# main.net
KiCad netlist of a schematic drawn in Altium Designer
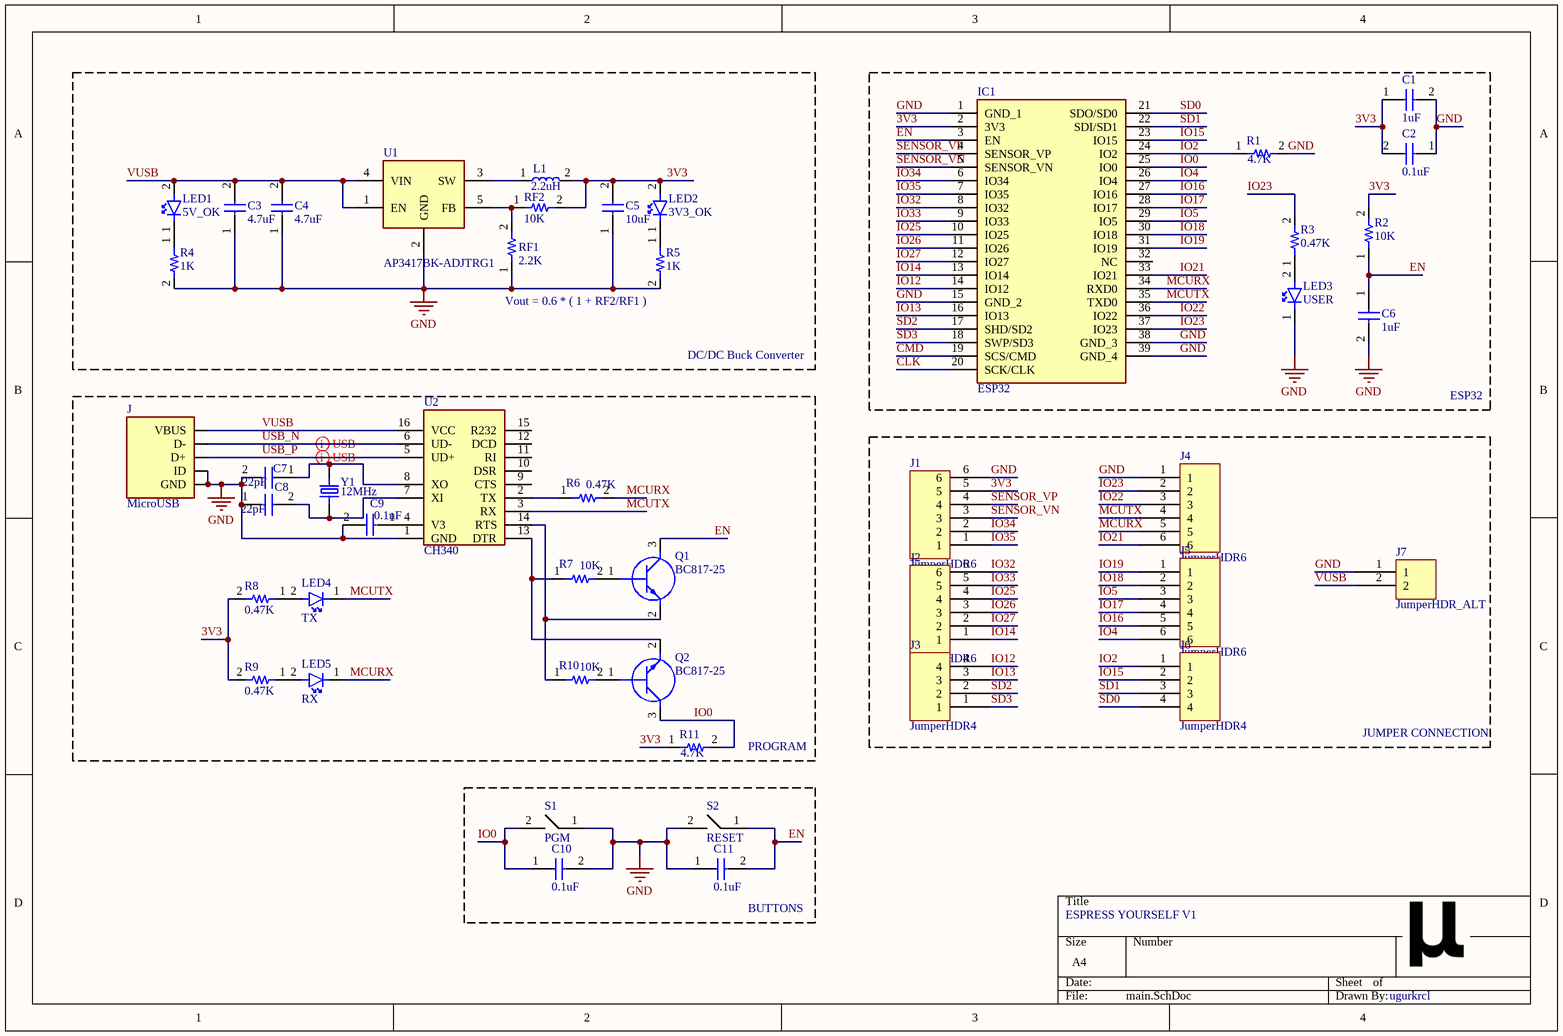
[diagram p0: main.SchDoc]

(export (version "E")
  (design (tool "Eeschema 10.0.6"))
  (components
    (comp (ref "C1")
      (value "1uF")
      (footprint "0805 Capacitor")
      (description "Capacitor")
      (fields
        (field (name "MANUFACTURER_PART_NUMBER") "C3216C0G1H682J060AA")
        (field (name "MOUSER PART NUMBER") "810-C3216C0G1H682J-1")
      )
      (libsource (lib "uAltiumLib") (part "0805 Capacitor"))
    )
    (comp (ref "C2")
      (value "0.1uF")
      (footprint "0603 Capacitor")
      (description "Capacitor")
      (fields
        (field (name "MANUFACTURER_PART_NUMBER") "06031A120JAT2A")
        (field (name "MOUSER PART NUMBER") "581-06031A120J")
      )
      (libsource (lib "uAltiumLib") (part "0603 Capacitor"))
    )
    (comp (ref "C3")
      (value "4.7uF")
      (footprint "0805 Capacitor")
      (description "Capacitor")
      (fields
        (field (name "MANUFACTURER_PART_NUMBER") "C3216C0G1H682J060AA")
        (field (name "MOUSER PART NUMBER") "810-C3216C0G1H682J-1")
      )
      (libsource (lib "uAltiumLib") (part "0805 Capacitor"))
    )
    (comp (ref "C4")
      (value "4.7uF")
      (footprint "0805 Capacitor")
      (description "Capacitor")
      (fields
        (field (name "MANUFACTURER_PART_NUMBER") "C3216C0G1H682J060AA")
        (field (name "MOUSER PART NUMBER") "810-C3216C0G1H682J-1")
      )
      (libsource (lib "uAltiumLib") (part "0805 Capacitor"))
    )
    (comp (ref "C5")
      (value "10uF")
      (footprint "0805 Capacitor")
      (description "Capacitor")
      (fields
        (field (name "MANUFACTURER_PART_NUMBER") "C3216C0G1H682J060AA")
        (field (name "MOUSER PART NUMBER") "810-C3216C0G1H682J-1")
      )
      (libsource (lib "uAltiumLib") (part "0805 Capacitor"))
    )
    (comp (ref "C6")
      (value "1uF")
      (footprint "0603 Capacitor")
      (description "Capacitor")
      (fields
        (field (name "MANUFACTURER_PART_NUMBER") "06031A120JAT2A")
        (field (name "MOUSER PART NUMBER") "581-06031A120J")
      )
      (libsource (lib "uAltiumLib") (part "0603 Capacitor"))
    )
    (comp (ref "C7")
      (value "22pF")
      (footprint "0603 Capacitor")
      (description "Capacitor")
      (fields
        (field (name "MANUFACTURER_PART_NUMBER") "06031A120JAT2A")
        (field (name "MOUSER PART NUMBER") "581-06031A120J")
      )
      (libsource (lib "uAltiumLib") (part "0603 Capacitor"))
    )
    (comp (ref "C8")
      (value "22pF")
      (footprint "0603 Capacitor")
      (description "Capacitor")
      (fields
        (field (name "MANUFACTURER_PART_NUMBER") "06031A120JAT2A")
        (field (name "MOUSER PART NUMBER") "581-06031A120J")
      )
      (libsource (lib "uAltiumLib") (part "0603 Capacitor"))
    )
    (comp (ref "C9")
      (value "0.1uF")
      (footprint "0603 Capacitor")
      (description "Capacitor")
      (fields
        (field (name "MANUFACTURER_PART_NUMBER") "06031A120JAT2A")
        (field (name "MOUSER PART NUMBER") "581-06031A120J")
      )
      (libsource (lib "uAltiumLib") (part "0603 Capacitor"))
    )
    (comp (ref "C10")
      (value "0.1uF")
      (footprint "0603 Capacitor")
      (description "Capacitor")
      (fields
        (field (name "MANUFACTURER_PART_NUMBER") "06031A120JAT2A")
        (field (name "MOUSER PART NUMBER") "581-06031A120J")
      )
      (libsource (lib "uAltiumLib") (part "0603 Capacitor"))
    )
    (comp (ref "C11")
      (value "0.1uF")
      (footprint "0603 Capacitor")
      (description "Capacitor")
      (fields
        (field (name "MANUFACTURER_PART_NUMBER") "06031A120JAT2A")
        (field (name "MOUSER PART NUMBER") "581-06031A120J")
      )
      (libsource (lib "uAltiumLib") (part "0603 Capacitor"))
    )
    (comp (ref "IC1")
      (value "ESP32")
      (footprint "ESP32")
      (description "Integrated Circuit")
      (fields
        (field (name "MANUFACTURER_PART_NUMBER") "ESP-WROOM-32D")
        (field (name "MOUSER PART NUMBER") "356-ESP-WROOM-32D")
      )
      (libsource (lib "uAltiumLib") (part "ESP32"))
    )
    (comp (ref "J")
      (value "MicroUSB")
      (footprint "MicroUSB")
      (fields (field (name "MP") "ZX62-B-5PA") (field (name "MF") "Hirose"))
      (libsource (lib "uAltiumLib") (part "MicroUSB"))
    )
    (comp (ref "J1")
      (value "JumperHDR6")
      (footprint "JumperHDR6")
      (libsource (lib "uAltiumLib") (part "JumperHDR6"))
    )
    (comp (ref "J2")
      (value "JumperHDR6")
      (footprint "JumperHDR6")
      (libsource (lib "uAltiumLib") (part "JumperHDR6"))
    )
    (comp (ref "J3")
      (value "JumperHDR4")
      (footprint "JumperHDR4")
      (libsource (lib "uAltiumLib") (part "JumperHDR4"))
    )
    (comp (ref "J4") (value "JumperHDR6") (footprint "JumperHDR6") (libsource (lib "") (part "JumperHDR6_1")))
    (comp (ref "J5") (value "JumperHDR6") (footprint "JumperHDR6") (libsource (lib "") (part "JumperHDR6_1")))
    (comp (ref "J6") (value "JumperHDR4") (footprint "JumperHDR4") (libsource (lib "") (part "JumperHDR4_1")))
    (comp (ref "J7")
      (value "JumperHDR_ALT")
      (footprint "JumperHDR")
      (libsource (lib "Schlib1") (part "JumperHDR_ALT"))
    )
    (comp (ref "L1")
      (value "2.2uH")
      (footprint "PcbLib1:INDUCTOR_3x3.5")
      (description "Inductor")
      (fields (field (name "MANUFACTURER_PART_NUMBER") "CD32-4R7M"))
      (libsource (lib "Schlib1") (part "INDUCTOR_3x3.5"))
    )
    (comp (ref "LED1")
      (value "5V_OK")
      (footprint "0603 LED")
      (description "LED")
      (fields
        (field (name "MANUFACTURER_PART_NUMBER") "150060GS55040")
        (field (name "MOUSER PART NUMBER") "710-150060GS55040")
      )
      (libsource (lib "Schlib1") (part "0603 LED"))
    )
    (comp (ref "LED2")
      (value "3V3_OK")
      (footprint "0603 LED")
      (description "LED")
      (fields
        (field (name "MANUFACTURER_PART_NUMBER") "150060GS55040")
        (field (name "MOUSER PART NUMBER") "710-150060GS55040")
      )
      (libsource (lib "Schlib1") (part "0603 LED"))
    )
    (comp (ref "LED3")
      (value "USER")
      (footprint "0603 LED")
      (description "LED")
      (fields
        (field (name "MANUFACTURER_PART_NUMBER") "150060GS55040")
        (field (name "MOUSER PART NUMBER") "710-150060GS55040")
      )
      (libsource (lib "Schlib1") (part "0603 LED"))
    )
    (comp (ref "LED4")
      (value "TX")
      (footprint "0603 LED")
      (description "LED")
      (fields
        (field (name "MANUFACTURER_PART_NUMBER") "150060GS55040")
        (field (name "MOUSER PART NUMBER") "710-150060GS55040")
      )
      (libsource (lib "Schlib1") (part "0603 LED"))
    )
    (comp (ref "LED5")
      (value "RX")
      (footprint "0603 LED")
      (description "LED")
      (fields
        (field (name "MANUFACTURER_PART_NUMBER") "150060GS55040")
        (field (name "MOUSER PART NUMBER") "710-150060GS55040")
      )
      (libsource (lib "Schlib1") (part "0603 LED"))
    )
    (comp (ref "Q1")
      (value "BC817-25")
      (footprint "BC817")
      (description "Transistor BJT NPN")
      (libsource (lib "uAltiumLib") (part "BC817-25"))
    )
    (comp (ref "Q2")
      (value "BC817-25")
      (footprint "BC817")
      (description "Transistor BJT NPN")
      (libsource (lib "uAltiumLib") (part "BC817-25"))
    )
    (comp (ref "R1")
      (value "4.7K")
      (footprint "0603 Resistor")
      (description "Resistor")
      (fields
        (field (name "MANUFACTURER_PART_NUMBER") "CPF0603B100RE1")
        (field (name "MOUSER PART NUMBER") "279-CPF0603B100RE1")
      )
      (libsource (lib "uAltiumLib") (part "0603 Resistor"))
    )
    (comp (ref "R2")
      (value "10K")
      (footprint "0603 Resistor")
      (description "Resistor")
      (fields
        (field (name "MANUFACTURER_PART_NUMBER") "CPF0603B100RE1")
        (field (name "MOUSER PART NUMBER") "279-CPF0603B100RE1")
      )
      (libsource (lib "uAltiumLib") (part "0603 Resistor"))
    )
    (comp (ref "R3")
      (value "0.47K")
      (footprint "0603 Resistor")
      (description "Resistor")
      (fields
        (field (name "MANUFACTURER_PART_NUMBER") "CPF0603B100RE1")
        (field (name "MOUSER PART NUMBER") "279-CPF0603B100RE1")
      )
      (libsource (lib "uAltiumLib") (part "0603 Resistor"))
    )
    (comp (ref "R4")
      (value "1K")
      (footprint "0603 Resistor")
      (description "Resistor")
      (fields
        (field (name "MANUFACTURER_PART_NUMBER") "CPF0603B100RE1")
        (field (name "MOUSER PART NUMBER") "279-CPF0603B100RE1")
      )
      (libsource (lib "uAltiumLib") (part "0603 Resistor"))
    )
    (comp (ref "R5")
      (value "1K")
      (footprint "0603 Resistor")
      (description "Resistor")
      (fields
        (field (name "MANUFACTURER_PART_NUMBER") "CPF0603B100RE1")
        (field (name "MOUSER PART NUMBER") "279-CPF0603B100RE1")
      )
      (libsource (lib "uAltiumLib") (part "0603 Resistor"))
    )
    (comp (ref "R6")
      (value "0.47K")
      (footprint "0603 Resistor")
      (description "Resistor")
      (fields
        (field (name "MANUFACTURER_PART_NUMBER") "CPF0603B100RE1")
        (field (name "MOUSER PART NUMBER") "279-CPF0603B100RE1")
      )
      (libsource (lib "uAltiumLib") (part "0603 Resistor"))
    )
    (comp (ref "R7")
      (value "10K")
      (footprint "0603 Resistor")
      (description "Resistor")
      (fields
        (field (name "MANUFACTURER_PART_NUMBER") "CPF0603B100RE1")
        (field (name "MOUSER PART NUMBER") "279-CPF0603B100RE1")
      )
      (libsource (lib "uAltiumLib") (part "0603 Resistor"))
    )
    (comp (ref "R8")
      (value "0.47K")
      (footprint "0603 Resistor")
      (description "Resistor")
      (fields
        (field (name "MANUFACTURER_PART_NUMBER") "CPF0603B100RE1")
        (field (name "MOUSER PART NUMBER") "279-CPF0603B100RE1")
      )
      (libsource (lib "uAltiumLib") (part "0603 Resistor"))
    )
    (comp (ref "R9")
      (value "0.47K")
      (footprint "0603 Resistor")
      (description "Resistor")
      (fields
        (field (name "MANUFACTURER_PART_NUMBER") "CPF0603B100RE1")
        (field (name "MOUSER PART NUMBER") "279-CPF0603B100RE1")
      )
      (libsource (lib "uAltiumLib") (part "0603 Resistor"))
    )
    (comp (ref "R10")
      (value "10K")
      (footprint "0603 Resistor")
      (description "Resistor")
      (fields
        (field (name "MANUFACTURER_PART_NUMBER") "CPF0603B100RE1")
        (field (name "MOUSER PART NUMBER") "279-CPF0603B100RE1")
      )
      (libsource (lib "uAltiumLib") (part "0603 Resistor"))
    )
    (comp (ref "R11")
      (value "4.7K")
      (footprint "0603 Resistor")
      (description "Resistor")
      (fields
        (field (name "MANUFACTURER_PART_NUMBER") "CPF0603B100RE1")
        (field (name "MOUSER PART NUMBER") "279-CPF0603B100RE1")
      )
      (libsource (lib "uAltiumLib") (part "0603 Resistor"))
    )
    (comp (ref "RF1")
      (value "2.2K")
      (footprint "0603 Resistor")
      (description "Resistor")
      (fields
        (field (name "MANUFACTURER_PART_NUMBER") "CPF0603B100RE1")
        (field (name "MOUSER PART NUMBER") "279-CPF0603B100RE1")
      )
      (libsource (lib "uAltiumLib") (part "0603 Resistor"))
    )
    (comp (ref "RF2")
      (value "10K")
      (footprint "0603 Resistor")
      (description "Resistor")
      (fields
        (field (name "MANUFACTURER_PART_NUMBER") "CPF0603B100RE1")
        (field (name "MOUSER PART NUMBER") "279-CPF0603B100RE1")
      )
      (libsource (lib "uAltiumLib") (part "0603 Resistor"))
    )
    (comp (ref "S1")
      (value "PGM")
      (footprint "TACT SWITCH SMD")
      (fields (field (name "MP") "B3F-1000") (field (name "MF") "Omron"))
      (libsource (lib "uAltiumLib") (part "TACT SWITCH SMD"))
    )
    (comp (ref "S2")
      (value "RESET")
      (footprint "TACT SWITCH SMD")
      (fields (field (name "MP") "B3F-1000") (field (name "MF") "Omron"))
      (libsource (lib "uAltiumLib") (part "TACT SWITCH SMD"))
    )
    (comp (ref "U1")
      (value "AP3417BK-ADJTRG1")
      (footprint "SOT BUCK")
      (description "Power Supply")
      (fields (field (name "MOUSER PART NUMBER") "621-AP3417BK-ADJTRG1"))
      (libsource (lib "Schlib1") (part "AP3417BK-ADJTRG1"))
    )
    (comp (ref "U2")
      (value "CH340")
      (footprint "ch340g-SOIC16")
      (fields (field (name "MF") "Eaton"))
      (libsource (lib "Schlib1") (part "CH340"))
    )
    (comp (ref "Y1")
      (value "12MHz")
      (footprint "Crystal-HC49")
      (fields
        (field (name "DIGI-KEY_PART_NUMBER") "X1115-ND")
        (field (name "MF") "ECS Inc.")
        (field (name "MP") "ECS-80-18-4XDN")
      )
      (libsource (lib "uAltiumLib") (part "HC49 Crystal"))
    )
  )
  (nets
    (net (code "1") (name "/3V3") (class "Default")
      (node (ref "C1") (pin "1") (pinfunction "1_1") (pintype "passive"))
      (node (ref "C2") (pin "2") (pinfunction "2_2") (pintype "passive"))
      (node (ref "C5") (pin "2") (pinfunction "2_2") (pintype "passive"))
      (node (ref "IC1") (pin "2") (pinfunction "3V3_2") (pintype "passive"))
      (node (ref "J1") (pin "5") (pinfunction "5_5") (pintype "passive"))
      (node (ref "L1") (pin "2") (pinfunction "2_2") (pintype "passive"))
      (node (ref "LED2") (pin "2") (pinfunction "A_2") (pintype "passive"))
      (node (ref "R11") (pin "1") (pinfunction "1_1") (pintype "passive"))
      (node (ref "R2") (pin "2") (pinfunction "2_2") (pintype "passive"))
      (node (ref "R8") (pin "2") (pinfunction "2_2") (pintype "passive"))
      (node (ref "R9") (pin "2") (pinfunction "2_2") (pintype "passive"))
      (node (ref "RF2") (pin "2") (pinfunction "2_2") (pintype "passive"))
    )
    (net (code "2") (name "/CLK") (class "Default")
      (node (ref "IC1") (pin "20") (pinfunction "SCK/CLK_20") (pintype "passive"))
    )
    (net (code "3") (name "/CMD") (class "Default")
      (node (ref "IC1") (pin "19") (pinfunction "SCS/CMD_19") (pintype "passive"))
    )
    (net (code "4") (name "/EN") (class "Default")
      (node (ref "C11") (pin "2") (pinfunction "2_2") (pintype "passive"))
      (node (ref "C6") (pin "1") (pinfunction "1_1") (pintype "passive"))
      (node (ref "IC1") (pin "3") (pinfunction "EN_3") (pintype "passive"))
      (node (ref "Q1") (pin "3") (pinfunction "C_3") (pintype "passive"))
      (node (ref "R2") (pin "1") (pinfunction "1_1") (pintype "passive"))
      (node (ref "S2") (pin "1") (pintype "passive"))
    )
    (net (code "5") (name "/IO0") (class "Default")
      (node (ref "C10") (pin "1") (pinfunction "1_1") (pintype "passive"))
      (node (ref "IC1") (pin "25") (pinfunction "IO0_25") (pintype "passive"))
      (node (ref "Q2") (pin "3") (pinfunction "C_3") (pintype "passive"))
      (node (ref "R11") (pin "2") (pinfunction "2_2") (pintype "passive"))
      (node (ref "S1") (pin "2") (pintype "passive"))
    )
    (net (code "6") (name "/IO2") (class "Default")
      (node (ref "IC1") (pin "24") (pinfunction "IO2_24") (pintype "passive"))
      (node (ref "J6") (pin "1") (pinfunction "1_1") (pintype "passive"))
      (node (ref "R1") (pin "1") (pinfunction "1_1") (pintype "passive"))
    )
    (net (code "7") (name "/IO4") (class "Default")
      (node (ref "IC1") (pin "26") (pinfunction "IO4_26") (pintype "passive"))
      (node (ref "J5") (pin "6") (pinfunction "6_6") (pintype "passive"))
    )
    (net (code "8") (name "/IO5") (class "Default")
      (node (ref "IC1") (pin "29") (pinfunction "IO5_29") (pintype "passive"))
      (node (ref "J5") (pin "3") (pinfunction "3_3") (pintype "passive"))
    )
    (net (code "9") (name "/IO12") (class "Default")
      (node (ref "IC1") (pin "14") (pinfunction "IO12_14") (pintype "passive"))
      (node (ref "J3") (pin "4") (pinfunction "4_4") (pintype "passive"))
    )
    (net (code "10") (name "/IO13") (class "Default")
      (node (ref "IC1") (pin "16") (pinfunction "IO13_16") (pintype "passive"))
      (node (ref "J3") (pin "3") (pinfunction "3_3") (pintype "passive"))
    )
    (net (code "11") (name "/IO14") (class "Default")
      (node (ref "IC1") (pin "13") (pinfunction "IO14_13") (pintype "passive"))
      (node (ref "J2") (pin "1") (pinfunction "1_1") (pintype "passive"))
    )
    (net (code "12") (name "/IO15") (class "Default")
      (node (ref "IC1") (pin "23") (pinfunction "IO15_23") (pintype "passive"))
      (node (ref "J6") (pin "2") (pinfunction "2_2") (pintype "passive"))
    )
    (net (code "13") (name "/IO16") (class "Default")
      (node (ref "IC1") (pin "27") (pinfunction "IO16_27") (pintype "passive"))
      (node (ref "J5") (pin "5") (pinfunction "5_5") (pintype "passive"))
    )
    (net (code "14") (name "/IO17") (class "Default")
      (node (ref "IC1") (pin "28") (pinfunction "IO17_28") (pintype "passive"))
      (node (ref "J5") (pin "4") (pinfunction "4_4") (pintype "passive"))
    )
    (net (code "15") (name "/IO18") (class "Default")
      (node (ref "IC1") (pin "30") (pinfunction "IO18_30") (pintype "passive"))
      (node (ref "J5") (pin "2") (pinfunction "2_2") (pintype "passive"))
    )
    (net (code "16") (name "/IO19") (class "Default")
      (node (ref "IC1") (pin "31") (pinfunction "IO19_31") (pintype "passive"))
      (node (ref "J5") (pin "1") (pinfunction "1_1") (pintype "passive"))
    )
    (net (code "17") (name "/IO21") (class "Default")
      (node (ref "IC1") (pin "33") (pinfunction "IO21_33") (pintype "passive"))
      (node (ref "J4") (pin "6") (pinfunction "6_6") (pintype "passive"))
    )
    (net (code "18") (name "/IO22") (class "Default")
      (node (ref "IC1") (pin "36") (pinfunction "IO22_36") (pintype "passive"))
      (node (ref "J4") (pin "3") (pinfunction "3_3") (pintype "passive"))
    )
    (net (code "19") (name "/IO23") (class "Default")
      (node (ref "IC1") (pin "37") (pinfunction "IO23_37") (pintype "passive"))
      (node (ref "J4") (pin "2") (pinfunction "2_2") (pintype "passive"))
      (node (ref "R3") (pin "2") (pinfunction "2_2") (pintype "passive"))
    )
    (net (code "20") (name "/IO25") (class "Default")
      (node (ref "IC1") (pin "10") (pinfunction "IO25_10") (pintype "passive"))
      (node (ref "J2") (pin "4") (pinfunction "4_4") (pintype "passive"))
    )
    (net (code "21") (name "/IO26") (class "Default")
      (node (ref "IC1") (pin "11") (pinfunction "IO26_11") (pintype "passive"))
      (node (ref "J2") (pin "3") (pinfunction "3_3") (pintype "passive"))
    )
    (net (code "22") (name "/IO27") (class "Default")
      (node (ref "IC1") (pin "12") (pinfunction "IO27_12") (pintype "passive"))
      (node (ref "J2") (pin "2") (pinfunction "2_2") (pintype "passive"))
    )
    (net (code "23") (name "/IO32") (class "Default")
      (node (ref "IC1") (pin "8") (pinfunction "IO32_8") (pintype "passive"))
      (node (ref "J2") (pin "6") (pinfunction "6_6") (pintype "passive"))
    )
    (net (code "24") (name "/IO33") (class "Default")
      (node (ref "IC1") (pin "9") (pinfunction "IO33_9") (pintype "passive"))
      (node (ref "J2") (pin "5") (pinfunction "5_5") (pintype "passive"))
    )
    (net (code "25") (name "/IO34") (class "Default")
      (node (ref "IC1") (pin "6") (pinfunction "IO34_6") (pintype "passive"))
      (node (ref "J1") (pin "2") (pinfunction "2_2") (pintype "passive"))
    )
    (net (code "26") (name "/IO35") (class "Default")
      (node (ref "IC1") (pin "7") (pinfunction "IO35_7") (pintype "passive"))
      (node (ref "J1") (pin "1") (pinfunction "1_1") (pintype "passive"))
    )
    (net (code "27") (name "/MCURX") (class "Default")
      (node (ref "IC1") (pin "34") (pinfunction "RXD0_34") (pintype "passive"))
      (node (ref "J4") (pin "5") (pinfunction "5_5") (pintype "passive"))
      (node (ref "LED5") (pin "1") (pinfunction "K_1") (pintype "passive"))
      (node (ref "R6") (pin "2") (pinfunction "2_2") (pintype "passive"))
    )
    (net (code "28") (name "/MCUTX") (class "Default")
      (node (ref "IC1") (pin "35") (pinfunction "TXD0_35") (pintype "passive"))
      (node (ref "J4") (pin "4") (pinfunction "4_4") (pintype "passive"))
      (node (ref "LED4") (pin "1") (pinfunction "K_1") (pintype "passive"))
      (node (ref "U2") (pin "3") (pinfunction "RX_3") (pintype "passive"))
    )
    (net (code "29") (name "/SD0") (class "Default")
      (node (ref "IC1") (pin "21") (pinfunction "SDO/SD0_21") (pintype "passive"))
      (node (ref "J6") (pin "4") (pinfunction "4_4") (pintype "passive"))
    )
    (net (code "30") (name "/SD1") (class "Default")
      (node (ref "IC1") (pin "22") (pinfunction "SDI/SD1_22") (pintype "passive"))
      (node (ref "J6") (pin "3") (pinfunction "3_3") (pintype "passive"))
    )
    (net (code "31") (name "/SD2") (class "Default")
      (node (ref "IC1") (pin "17") (pinfunction "SHD/SD2_17") (pintype "passive"))
      (node (ref "J3") (pin "2") (pinfunction "2_2") (pintype "passive"))
    )
    (net (code "32") (name "/SD3") (class "Default")
      (node (ref "IC1") (pin "18") (pinfunction "SWP/SD3_18") (pintype "passive"))
      (node (ref "J3") (pin "1") (pinfunction "1_1") (pintype "passive"))
    )
    (net (code "33") (name "/SENSOR_VN") (class "Default")
      (node (ref "IC1") (pin "5") (pinfunction "SENSOR_VN_5") (pintype "passive"))
      (node (ref "J1") (pin "3") (pinfunction "3_3") (pintype "passive"))
    )
    (net (code "34") (name "/SENSOR_VP") (class "Default")
      (node (ref "IC1") (pin "4") (pinfunction "SENSOR_VP_4") (pintype "passive"))
      (node (ref "J1") (pin "4") (pinfunction "4_4") (pintype "passive"))
    )
    (net (code "35") (name "/USB_N") (class "Default")
      (node (ref "J") (pin "2") (pinfunction "D-_2") (pintype "passive"))
      (node (ref "U2") (pin "6") (pinfunction "UD-_6") (pintype "passive"))
    )
    (net (code "36") (name "/USB_P") (class "Default")
      (node (ref "J") (pin "3") (pinfunction "D+_3") (pintype "passive"))
      (node (ref "U2") (pin "5") (pinfunction "UD+_5") (pintype "passive"))
    )
    (net (code "37") (name "/VUSB") (class "Default")
      (node (ref "C3") (pin "2") (pinfunction "2_2") (pintype "passive"))
      (node (ref "C4") (pin "2") (pinfunction "2_2") (pintype "passive"))
      (node (ref "J") (pin "1") (pinfunction "VBUS_1") (pintype "power_in"))
      (node (ref "J7") (pin "2") (pinfunction "2_2") (pintype "passive"))
      (node (ref "LED1") (pin "2") (pinfunction "A_2") (pintype "passive"))
      (node (ref "U1") (pin "1") (pinfunction "EN_1") (pintype "passive"))
      (node (ref "U1") (pin "4") (pinfunction "VIN_4") (pintype "passive"))
      (node (ref "U2") (pin "16") (pinfunction "VCC_16") (pintype "passive"))
    )
    (net (code "38") (name "GND") (class "Default")
      (node (ref "C1") (pin "2") (pinfunction "2_2") (pintype "passive"))
      (node (ref "C10") (pin "2") (pinfunction "2_2") (pintype "passive"))
      (node (ref "C11") (pin "1") (pinfunction "1_1") (pintype "passive"))
      (node (ref "C2") (pin "1") (pinfunction "1_1") (pintype "passive"))
      (node (ref "C3") (pin "1") (pinfunction "1_1") (pintype "passive"))
      (node (ref "C4") (pin "1") (pinfunction "1_1") (pintype "passive"))
      (node (ref "C5") (pin "1") (pinfunction "1_1") (pintype "passive"))
      (node (ref "C6") (pin "2") (pinfunction "2_2") (pintype "passive"))
      (node (ref "C7") (pin "2") (pinfunction "2_2") (pintype "passive"))
      (node (ref "C8") (pin "1") (pinfunction "1_1") (pintype "passive"))
      (node (ref "C9") (pin "2") (pinfunction "2_2") (pintype "passive"))
      (node (ref "IC1") (pin "1") (pinfunction "GND_1_1") (pintype "passive"))
      (node (ref "IC1") (pin "15") (pinfunction "GND_2_15") (pintype "passive"))
      (node (ref "IC1") (pin "38") (pinfunction "GND_3_38") (pintype "passive"))
      (node (ref "IC1") (pin "39") (pinfunction "GND_4_39") (pintype "passive"))
      (node (ref "J") (pin "4") (pinfunction "ID_4") (pintype "passive"))
      (node (ref "J") (pin "5") (pinfunction "GND_5") (pintype "power_in"))
      (node (ref "J1") (pin "6") (pinfunction "6_6") (pintype "passive"))
      (node (ref "J4") (pin "1") (pinfunction "1_1") (pintype "passive"))
      (node (ref "J7") (pin "1") (pinfunction "1_1") (pintype "passive"))
      (node (ref "LED3") (pin "1") (pinfunction "K_1") (pintype "passive"))
      (node (ref "R1") (pin "2") (pinfunction "2_2") (pintype "passive"))
      (node (ref "R4") (pin "2") (pinfunction "2_2") (pintype "passive"))
      (node (ref "R5") (pin "2") (pinfunction "2_2") (pintype "passive"))
      (node (ref "RF1") (pin "1") (pinfunction "1_1") (pintype "passive"))
      (node (ref "S1") (pin "1") (pintype "passive"))
      (node (ref "S2") (pin "2") (pintype "passive"))
      (node (ref "U1") (pin "2") (pinfunction "GND_2") (pintype "passive"))
      (node (ref "U2") (pin "1") (pinfunction "GND_1") (pintype "power_in"))
    )
    (net (code "39") (name "Net-(LED1-K)") (class "Default")
      (node (ref "LED1") (pin "1") (pinfunction "K_1") (pintype "passive"))
      (node (ref "R4") (pin "1") (pinfunction "1_1") (pintype "passive"))
    )
    (net (code "40") (name "Net-(LED2-K)") (class "Default")
      (node (ref "LED2") (pin "1") (pinfunction "K_1") (pintype "passive"))
      (node (ref "R5") (pin "1") (pinfunction "1_1") (pintype "passive"))
    )
    (net (code "41") (name "Net-(LED3-A)") (class "Default")
      (node (ref "LED3") (pin "2") (pinfunction "A_2") (pintype "passive"))
      (node (ref "R3") (pin "1") (pinfunction "1_1") (pintype "passive"))
    )
    (net (code "42") (name "Net-(LED4-A)") (class "Default")
      (node (ref "LED4") (pin "2") (pinfunction "A_2") (pintype "passive"))
      (node (ref "R8") (pin "1") (pinfunction "1_1") (pintype "passive"))
    )
    (net (code "43") (name "Net-(LED5-A)") (class "Default")
      (node (ref "LED5") (pin "2") (pinfunction "A_2") (pintype "passive"))
      (node (ref "R9") (pin "1") (pinfunction "1_1") (pintype "passive"))
    )
    (net (code "44") (name "Net-(Q1-B)") (class "Default")
      (node (ref "Q1") (pin "1") (pinfunction "B_1") (pintype "passive"))
      (node (ref "R7") (pin "2") (pinfunction "2_2") (pintype "passive"))
    )
    (net (code "45") (name "Net-(Q1-E)") (class "Default")
      (node (ref "Q1") (pin "2") (pinfunction "E_2") (pintype "passive"))
      (node (ref "R10") (pin "1") (pinfunction "1_1") (pintype "passive"))
      (node (ref "U2") (pin "14") (pinfunction "RTS_14") (pintype "passive"))
    )
    (net (code "46") (name "Net-(Q2-B)") (class "Default")
      (node (ref "Q2") (pin "1") (pinfunction "B_1") (pintype "passive"))
      (node (ref "R10") (pin "2") (pinfunction "2_2") (pintype "passive"))
    )
    (net (code "47") (name "Net-(Q2-E)") (class "Default")
      (node (ref "Q2") (pin "2") (pinfunction "E_2") (pintype "passive"))
      (node (ref "R7") (pin "1") (pinfunction "1_1") (pintype "passive"))
      (node (ref "U2") (pin "13") (pinfunction "DTR_13") (pintype "passive"))
    )
    (net (code "48") (name "Net-(U1-FB)") (class "Default")
      (node (ref "RF1") (pin "2") (pinfunction "2_2") (pintype "passive"))
      (node (ref "RF2") (pin "1") (pinfunction "1_1") (pintype "passive"))
      (node (ref "U1") (pin "5") (pinfunction "FB_5") (pintype "passive"))
    )
    (net (code "49") (name "Net-(U1-SW)") (class "Default")
      (node (ref "L1") (pin "1") (pinfunction "1_1") (pintype "passive"))
      (node (ref "U1") (pin "3") (pinfunction "SW_3") (pintype "passive"))
    )
    (net (code "50") (name "Net-(U2-TX)") (class "Default")
      (node (ref "R6") (pin "1") (pinfunction "1_1") (pintype "passive"))
      (node (ref "U2") (pin "2") (pinfunction "TX_2") (pintype "passive"))
    )
    (net (code "51") (name "Net-(U2-V3)") (class "Default")
      (node (ref "C9") (pin "1") (pinfunction "1_1") (pintype "passive"))
      (node (ref "U2") (pin "4") (pinfunction "V3_4") (pintype "passive"))
    )
    (net (code "52") (name "Net-(U2-XI)") (class "Default")
      (node (ref "C8") (pin "2") (pinfunction "2_2") (pintype "passive"))
      (node (ref "U2") (pin "7") (pinfunction "XI_7") (pintype "passive"))
      (node (ref "Y1") (pin "1") (pinfunction "1_1") (pintype "passive"))
    )
    (net (code "53") (name "Net-(U2-XO)") (class "Default")
      (node (ref "C7") (pin "1") (pinfunction "1_1") (pintype "passive"))
      (node (ref "U2") (pin "8") (pinfunction "XO_8") (pintype "passive"))
      (node (ref "Y1") (pin "2") (pinfunction "2_2") (pintype "passive"))
    )
    (net (code "54") (name "unconnected-(IC1-NC-Pad32)") (class "Default")
      (node (ref "IC1") (pin "32") (pinfunction "NC_32") (pintype "passive"))
    )
    (net (code "55") (name "unconnected-(U2-CTS-Pad9)") (class "Default")
      (node (ref "U2") (pin "9") (pinfunction "CTS_9") (pintype "passive"))
    )
    (net (code "56") (name "unconnected-(U2-DCD-Pad12)") (class "Default")
      (node (ref "U2") (pin "12") (pinfunction "DCD_12") (pintype "passive"))
    )
    (net (code "57") (name "unconnected-(U2-DSR-Pad10)") (class "Default")
      (node (ref "U2") (pin "10") (pinfunction "DSR_10") (pintype "passive"))
    )
    (net (code "58") (name "unconnected-(U2-R232-Pad15)") (class "Default")
      (node (ref "U2") (pin "15") (pinfunction "R232_15") (pintype "passive"))
    )
    (net (code "59") (name "unconnected-(U2-RI-Pad11)") (class "Default")
      (node (ref "U2") (pin "11") (pinfunction "RI_11") (pintype "passive"))
    )
  )
)
